# V0_1.net
KiCad netlist of a schematic drawn in EAGLE
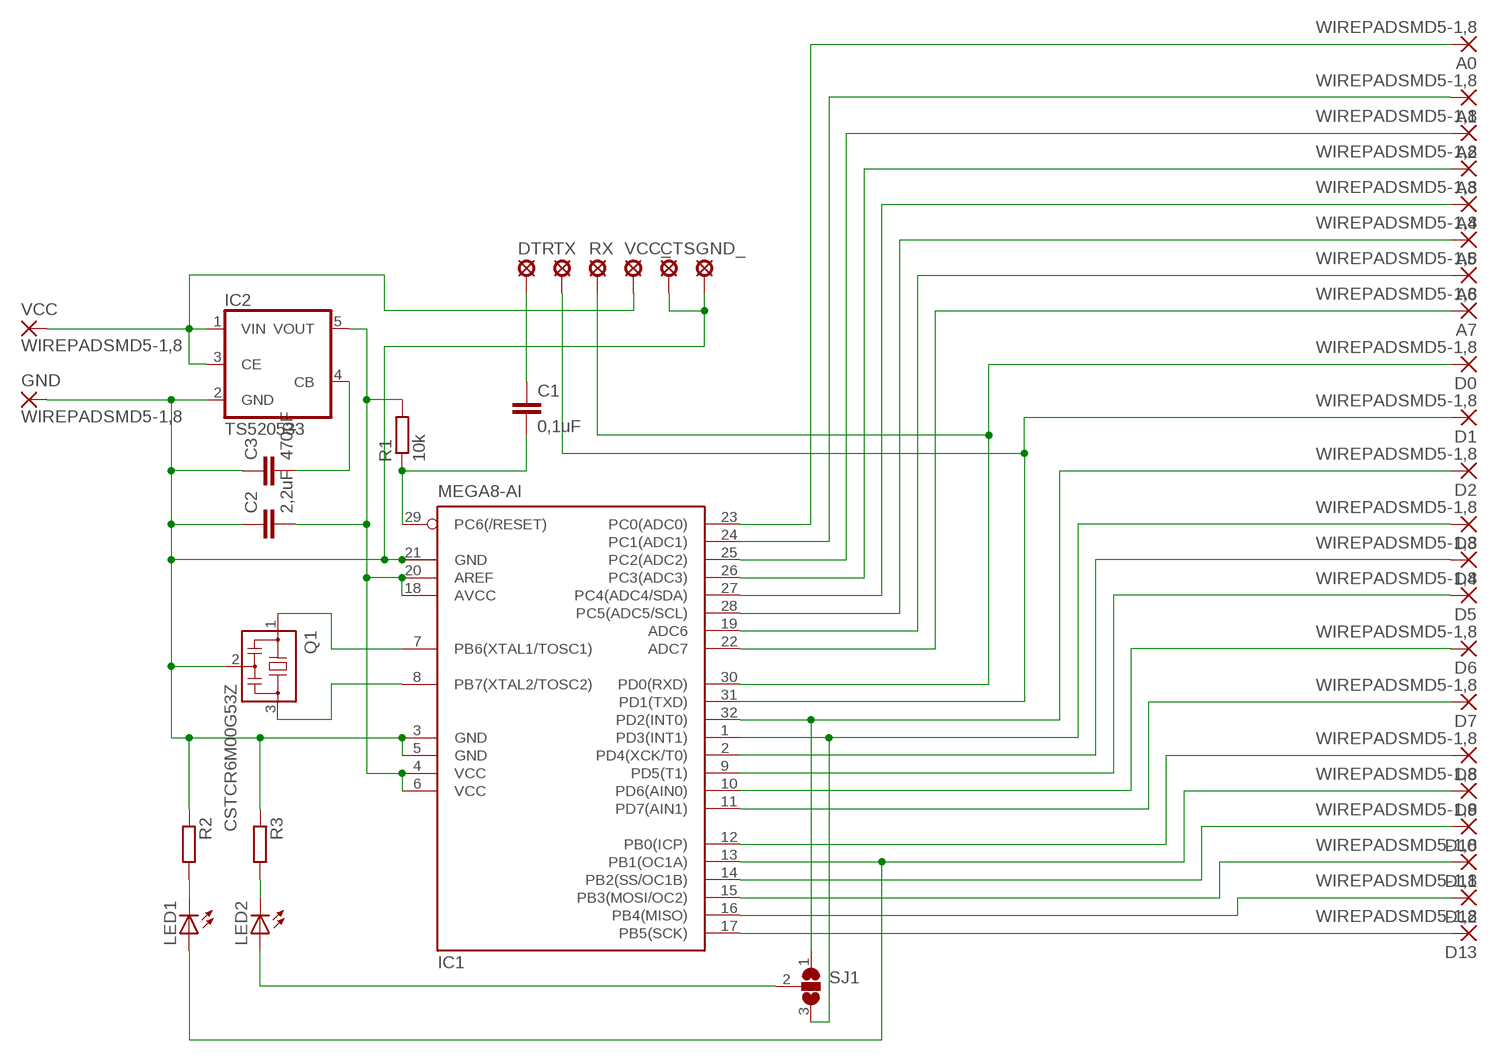
[diagram p0: schematic, sheet 1]

(export (version "E")
  (design (tool "Eeschema 10.0.6"))
  (components
    (comp (ref "A0")
      (value "WIREPADSMD5-1,8")
      (footprint "eagle-import:5-1,8")
      (libsource (lib "eagle-import") (part "WIREPADSMD5-1,8"))
    )
    (comp (ref "A1")
      (value "WIREPADSMD5-1,8")
      (footprint "eagle-import:5-1,8")
      (libsource (lib "eagle-import") (part "WIREPADSMD5-1,8"))
    )
    (comp (ref "A2")
      (value "WIREPADSMD5-1,8")
      (footprint "eagle-import:5-1,8")
      (libsource (lib "eagle-import") (part "WIREPADSMD5-1,8"))
    )
    (comp (ref "A3")
      (value "WIREPADSMD5-1,8")
      (footprint "eagle-import:5-1,8")
      (libsource (lib "eagle-import") (part "WIREPADSMD5-1,8"))
    )
    (comp (ref "A4")
      (value "WIREPADSMD5-1,8")
      (footprint "eagle-import:5-1,8")
      (libsource (lib "eagle-import") (part "WIREPADSMD5-1,8"))
    )
    (comp (ref "A5")
      (value "WIREPADSMD5-1,8")
      (footprint "eagle-import:5-1,8")
      (libsource (lib "eagle-import") (part "WIREPADSMD5-1,8"))
    )
    (comp (ref "A6")
      (value "WIREPADSMD5-1,8")
      (footprint "eagle-import:5-1,8")
      (libsource (lib "eagle-import") (part "WIREPADSMD5-1,8"))
    )
    (comp (ref "A7")
      (value "WIREPADSMD5-1,8")
      (footprint "eagle-import:5-1,8")
      (libsource (lib "eagle-import") (part "WIREPADSMD5-1,8"))
    )
    (comp (ref "C1")
      (value "0,1uF")
      (footprint "eagle-import:C0603")
      (libsource (lib "eagle-import") (part "C-EUC0603"))
    )
    (comp (ref "C2")
      (value "2,2uF")
      (footprint "eagle-import:C0603")
      (libsource (lib "eagle-import") (part "C-EUC0603"))
    )
    (comp (ref "C3")
      (value "470pF")
      (footprint "eagle-import:C0603")
      (libsource (lib "eagle-import") (part "C-EUC0603"))
    )
    (comp (ref "CTS")
      (value "LSP10")
      (footprint "eagle-import:LSP10")
      (libsource (lib "eagle-import") (part "LSP10"))
    )
    (comp (ref "D0")
      (value "WIREPADSMD5-1,8")
      (footprint "eagle-import:5-1,8")
      (libsource (lib "eagle-import") (part "WIREPADSMD5-1,8"))
    )
    (comp (ref "D1")
      (value "WIREPADSMD5-1,8")
      (footprint "eagle-import:5-1,8")
      (libsource (lib "eagle-import") (part "WIREPADSMD5-1,8"))
    )
    (comp (ref "D2")
      (value "WIREPADSMD5-1,8")
      (footprint "eagle-import:5-1,8")
      (libsource (lib "eagle-import") (part "WIREPADSMD5-1,8"))
    )
    (comp (ref "D3")
      (value "WIREPADSMD5-1,8")
      (footprint "eagle-import:5-1,8")
      (libsource (lib "eagle-import") (part "WIREPADSMD5-1,8"))
    )
    (comp (ref "D4")
      (value "WIREPADSMD5-1,8")
      (footprint "eagle-import:5-1,8")
      (libsource (lib "eagle-import") (part "WIREPADSMD5-1,8"))
    )
    (comp (ref "D5")
      (value "WIREPADSMD5-1,8")
      (footprint "eagle-import:5-1,8")
      (libsource (lib "eagle-import") (part "WIREPADSMD5-1,8"))
    )
    (comp (ref "D6")
      (value "WIREPADSMD5-1,8")
      (footprint "eagle-import:5-1,8")
      (libsource (lib "eagle-import") (part "WIREPADSMD5-1,8"))
    )
    (comp (ref "D7")
      (value "WIREPADSMD5-1,8")
      (footprint "eagle-import:5-1,8")
      (libsource (lib "eagle-import") (part "WIREPADSMD5-1,8"))
    )
    (comp (ref "D8")
      (value "WIREPADSMD5-1,8")
      (footprint "eagle-import:5-1,8")
      (libsource (lib "eagle-import") (part "WIREPADSMD5-1,8"))
    )
    (comp (ref "D9")
      (value "WIREPADSMD5-1,8")
      (footprint "eagle-import:5-1,8")
      (libsource (lib "eagle-import") (part "WIREPADSMD5-1,8"))
    )
    (comp (ref "D10")
      (value "WIREPADSMD5-1,8")
      (footprint "eagle-import:5-1,8")
      (libsource (lib "eagle-import") (part "WIREPADSMD5-1,8"))
    )
    (comp (ref "D11")
      (value "WIREPADSMD5-1,8")
      (footprint "eagle-import:5-1,8")
      (libsource (lib "eagle-import") (part "WIREPADSMD5-1,8"))
    )
    (comp (ref "D12")
      (value "WIREPADSMD5-1,8")
      (footprint "eagle-import:5-1,8")
      (libsource (lib "eagle-import") (part "WIREPADSMD5-1,8"))
    )
    (comp (ref "D13")
      (value "WIREPADSMD5-1,8")
      (footprint "eagle-import:5-1,8")
      (libsource (lib "eagle-import") (part "WIREPADSMD5-1,8"))
    )
    (comp (ref "DTR")
      (value "LSP10")
      (footprint "eagle-import:LSP10")
      (libsource (lib "eagle-import") (part "LSP10"))
    )
    (comp (ref "GND")
      (value "WIREPADSMD5-1,8")
      (footprint "eagle-import:5-1,8")
      (libsource (lib "eagle-import") (part "WIREPADSMD5-1,8"))
    )
    (comp (ref "GND_")
      (value "LSP10")
      (footprint "eagle-import:LSP10")
      (libsource (lib "eagle-import") (part "LSP10"))
    )
    (comp (ref "IC1")
      (value "MEGA8-AI")
      (footprint "eagle-import:TQFP32-08")
      (fields (field (name "MPN") "ATMEGA8-16AU") (field (name "MPN_1") "ATMEGA328P-16AU"))
      (libsource (lib "eagle-import") (part "MEGA8-AI"))
    )
    (comp (ref "IC2")
      (value "TS520533")
      (footprint "eagle-import:SOT25")
      (libsource (lib "eagle-import") (part "TS520533"))
    )
    (comp (ref "LED1")
      (value "LEDCHIP-LED0603")
      (footprint "eagle-import:CHIP-LED0603")
      (libsource (lib "eagle-import") (part "LEDCHIP-LED0603"))
    )
    (comp (ref "LED2")
      (value "LEDCHIP-LED0603")
      (footprint "eagle-import:CHIP-LED0603")
      (libsource (lib "eagle-import") (part "LEDCHIP-LED0603"))
    )
    (comp (ref "Q1")
      (value "CSTCR6M00G53Z")
      (footprint "eagle-import:CSTCR6M")
      (fields (field (name "MPN") "CSTCR6M00G53-R0"))
      (libsource (lib "eagle-import") (part "CSTCR6M00G53Z"))
    )
    (comp (ref "R1")
      (value "10k")
      (footprint "eagle-import:R0603")
      (libsource (lib "eagle-import") (part "R-EU_R0603"))
    )
    (comp (ref "R2")
      (value "R-EU_R0603")
      (footprint "eagle-import:R0603")
      (libsource (lib "eagle-import") (part "R-EU_R0603"))
    )
    (comp (ref "R3")
      (value "R-EU_R0603")
      (footprint "eagle-import:R0603")
      (libsource (lib "eagle-import") (part "R-EU_R0603"))
    )
    (comp (ref "RX")
      (value "LSP10")
      (footprint "eagle-import:LSP10")
      (libsource (lib "eagle-import") (part "LSP10"))
    )
    (comp (ref "SJ1")
      (value "SJ2W")
      (footprint "eagle-import:SJ_2")
      (libsource (lib "eagle-import") (part "SJ2W"))
    )
    (comp (ref "TX")
      (value "LSP10")
      (footprint "eagle-import:LSP10")
      (libsource (lib "eagle-import") (part "LSP10"))
    )
    (comp (ref "VCC")
      (value "WIREPADSMD5-1,8")
      (footprint "eagle-import:5-1,8")
      (libsource (lib "eagle-import") (part "WIREPADSMD5-1,8"))
    )
    (comp (ref "VCC_")
      (value "LSP10")
      (footprint "eagle-import:LSP10")
      (libsource (lib "eagle-import") (part "LSP10"))
    )
  )
  (nets
    (net (code "1") (name "Net-(A0-P)") (class "Default")
      (node (ref "A0") (pin "1") (pinfunction "P_1") (pintype "passive"))
      (node (ref "IC1") (pin "23") (pinfunction "PC0(ADC0)_23") (pintype "bidirectional"))
    )
    (net (code "2") (name "Net-(A1-P)") (class "Default")
      (node (ref "A1") (pin "1") (pinfunction "P_1") (pintype "passive"))
      (node (ref "IC1") (pin "24") (pinfunction "PC1(ADC1)_24") (pintype "bidirectional"))
    )
    (net (code "3") (name "Net-(A2-P)") (class "Default")
      (node (ref "A2") (pin "1") (pinfunction "P_1") (pintype "passive"))
      (node (ref "IC1") (pin "25") (pinfunction "PC2(ADC2)_25") (pintype "bidirectional"))
    )
    (net (code "4") (name "Net-(A3-P)") (class "Default")
      (node (ref "A3") (pin "1") (pinfunction "P_1") (pintype "passive"))
      (node (ref "IC1") (pin "26") (pinfunction "PC3(ADC3)_26") (pintype "bidirectional"))
    )
    (net (code "5") (name "Net-(A4-P)") (class "Default")
      (node (ref "A4") (pin "1") (pinfunction "P_1") (pintype "passive"))
      (node (ref "IC1") (pin "27") (pinfunction "PC4(ADC4/SDA)_27") (pintype "bidirectional"))
    )
    (net (code "6") (name "Net-(A5-P)") (class "Default")
      (node (ref "A5") (pin "1") (pinfunction "P_1") (pintype "passive"))
      (node (ref "IC1") (pin "28") (pinfunction "PC5(ADC5/SCL)_28") (pintype "bidirectional"))
    )
    (net (code "7") (name "Net-(A6-P)") (class "Default")
      (node (ref "A6") (pin "1") (pinfunction "P_1") (pintype "passive"))
      (node (ref "IC1") (pin "19") (pinfunction "ADC6_19") (pintype "bidirectional"))
    )
    (net (code "8") (name "Net-(A7-P)") (class "Default")
      (node (ref "A7") (pin "1") (pinfunction "P_1") (pintype "passive"))
      (node (ref "IC1") (pin "22") (pinfunction "ADC7_22") (pintype "bidirectional"))
    )
    (net (code "9") (name "Net-(C1-Pad1)") (class "Default")
      (node (ref "C1") (pin "1") (pinfunction "1_1") (pintype "passive"))
      (node (ref "DTR") (pin "MP") (pinfunction "MP_MP") (pintype "passive"))
    )
    (net (code "10") (name "Net-(D0-P)") (class "Default")
      (node (ref "D0") (pin "1") (pinfunction "P_1") (pintype "passive"))
      (node (ref "IC1") (pin "30") (pinfunction "PD0(RXD)_30") (pintype "bidirectional"))
      (node (ref "RX") (pin "MP") (pinfunction "MP_MP") (pintype "passive"))
    )
    (net (code "11") (name "Net-(D1-P)") (class "Default")
      (node (ref "D1") (pin "1") (pinfunction "P_1") (pintype "passive"))
      (node (ref "IC1") (pin "31") (pinfunction "PD1(TXD)_31") (pintype "bidirectional"))
      (node (ref "TX") (pin "MP") (pinfunction "MP_MP") (pintype "passive"))
    )
    (net (code "12") (name "Net-(D2-P)") (class "Default")
      (node (ref "D2") (pin "1") (pinfunction "P_1") (pintype "passive"))
      (node (ref "IC1") (pin "32") (pinfunction "PD2(INT0)_32") (pintype "bidirectional"))
      (node (ref "SJ1") (pin "1") (pinfunction "1_1") (pintype "passive"))
    )
    (net (code "13") (name "Net-(D3-P)") (class "Default")
      (node (ref "D3") (pin "1") (pinfunction "P_1") (pintype "passive"))
      (node (ref "IC1") (pin "1") (pinfunction "PD3(INT1)_1") (pintype "bidirectional"))
      (node (ref "SJ1") (pin "3") (pinfunction "3_3") (pintype "passive"))
    )
    (net (code "14") (name "Net-(D4-P)") (class "Default")
      (node (ref "D4") (pin "1") (pinfunction "P_1") (pintype "passive"))
      (node (ref "IC1") (pin "2") (pinfunction "PD4(XCK/T0)_2") (pintype "bidirectional"))
    )
    (net (code "15") (name "Net-(D5-P)") (class "Default")
      (node (ref "D5") (pin "1") (pinfunction "P_1") (pintype "passive"))
      (node (ref "IC1") (pin "9") (pinfunction "PD5(T1)_9") (pintype "bidirectional"))
    )
    (net (code "16") (name "Net-(D6-P)") (class "Default")
      (node (ref "D6") (pin "1") (pinfunction "P_1") (pintype "passive"))
      (node (ref "IC1") (pin "10") (pinfunction "PD6(AIN0)_10") (pintype "bidirectional"))
    )
    (net (code "17") (name "Net-(D7-P)") (class "Default")
      (node (ref "D7") (pin "1") (pinfunction "P_1") (pintype "passive"))
      (node (ref "IC1") (pin "11") (pinfunction "PD7(AIN1)_11") (pintype "bidirectional"))
    )
    (net (code "18") (name "Net-(D8-P)") (class "Default")
      (node (ref "D8") (pin "1") (pinfunction "P_1") (pintype "passive"))
      (node (ref "IC1") (pin "12") (pinfunction "PB0(ICP)_12") (pintype "bidirectional"))
    )
    (net (code "19") (name "Net-(D9-P)") (class "Default")
      (node (ref "D9") (pin "1") (pinfunction "P_1") (pintype "passive"))
      (node (ref "IC1") (pin "13") (pinfunction "PB1(OC1A)_13") (pintype "bidirectional"))
      (node (ref "LED1") (pin "A") (pinfunction "A_A") (pintype "passive"))
    )
    (net (code "20") (name "Net-(D10-P)") (class "Default")
      (node (ref "D10") (pin "1") (pinfunction "P_1") (pintype "passive"))
      (node (ref "IC1") (pin "14") (pinfunction "PB2(SS/OC1B)_14") (pintype "bidirectional"))
    )
    (net (code "21") (name "Net-(D11-P)") (class "Default")
      (node (ref "D11") (pin "1") (pinfunction "P_1") (pintype "passive"))
      (node (ref "IC1") (pin "15") (pinfunction "PB3(MOSI/OC2)_15") (pintype "bidirectional"))
    )
    (net (code "22") (name "Net-(D12-P)") (class "Default")
      (node (ref "D12") (pin "1") (pinfunction "P_1") (pintype "passive"))
      (node (ref "IC1") (pin "16") (pinfunction "PB4(MISO)_16") (pintype "bidirectional"))
    )
    (net (code "23") (name "Net-(D13-P)") (class "Default")
      (node (ref "D13") (pin "1") (pinfunction "P_1") (pintype "passive"))
      (node (ref "IC1") (pin "17") (pinfunction "PB5(SCK)_17") (pintype "bidirectional"))
    )
    (net (code "24") (name "Net-(GND-P)") (class "Default")
      (node (ref "C2") (pin "1") (pinfunction "1_1") (pintype "passive"))
      (node (ref "C3") (pin "1") (pinfunction "1_1") (pintype "passive"))
      (node (ref "CTS") (pin "MP") (pinfunction "MP_MP") (pintype "passive"))
      (node (ref "GND") (pin "1") (pinfunction "P_1") (pintype "passive"))
      (node (ref "GND_") (pin "MP") (pinfunction "MP_MP") (pintype "passive"))
      (node (ref "IC1") (pin "21") (pinfunction "GND_21") (pintype "power_in"))
      (node (ref "IC1") (pin "3") (pinfunction "GND_3") (pintype "power_in"))
      (node (ref "IC1") (pin "5") (pinfunction "GND_5") (pintype "power_in"))
      (node (ref "IC2") (pin "2") (pinfunction "GND_2") (pintype "passive"))
      (node (ref "Q1") (pin "2") (pinfunction "2_2") (pintype "passive"))
      (node (ref "R2") (pin "1") (pinfunction "1_1") (pintype "passive"))
      (node (ref "R3") (pin "1") (pinfunction "1_1") (pintype "passive"))
    )
    (net (code "25") (name "Net-(IC1-AREF)") (class "Default")
      (node (ref "C2") (pin "2") (pinfunction "2_2") (pintype "passive"))
      (node (ref "IC1") (pin "18") (pinfunction "AVCC_18") (pintype "power_in"))
      (node (ref "IC1") (pin "20") (pinfunction "AREF_20") (pintype "passive"))
      (node (ref "IC1") (pin "4") (pinfunction "VCC_4") (pintype "power_in"))
      (node (ref "IC1") (pin "6") (pinfunction "VCC_6") (pintype "power_in"))
      (node (ref "IC2") (pin "5") (pinfunction "VOUT_5") (pintype "passive"))
      (node (ref "R1") (pin "2") (pinfunction "2_2") (pintype "passive"))
    )
    (net (code "26") (name "Net-(IC1-PB6(XTAL1{slash}TOSC1))") (class "Default")
      (node (ref "IC1") (pin "7") (pinfunction "PB6(XTAL1/TOSC1)_7") (pintype "bidirectional"))
      (node (ref "Q1") (pin "1") (pinfunction "1_1") (pintype "passive"))
    )
    (net (code "27") (name "Net-(IC1-PB7(XTAL2{slash}TOSC2))") (class "Default")
      (node (ref "IC1") (pin "8") (pinfunction "PB7(XTAL2/TOSC2)_8") (pintype "bidirectional"))
      (node (ref "Q1") (pin "3") (pinfunction "3_3") (pintype "passive"))
    )
    (net (code "28") (name "Net-(IC1-PC6({slash}RESET))") (class "Default")
      (node (ref "C1") (pin "2") (pinfunction "2_2") (pintype "passive"))
      (node (ref "IC1") (pin "29") (pinfunction "PC6(/RESET)_29") (pintype "bidirectional"))
      (node (ref "R1") (pin "1") (pinfunction "1_1") (pintype "passive"))
    )
    (net (code "29") (name "Net-(IC2-CB)") (class "Default")
      (node (ref "C3") (pin "2") (pinfunction "2_2") (pintype "passive"))
      (node (ref "IC2") (pin "4") (pinfunction "CB_4") (pintype "input"))
    )
    (net (code "30") (name "Net-(IC2-CE)") (class "Default")
      (node (ref "IC2") (pin "1") (pinfunction "VIN_1") (pintype "input"))
      (node (ref "IC2") (pin "3") (pinfunction "CE_3") (pintype "input"))
      (node (ref "VCC") (pin "1") (pinfunction "P_1") (pintype "passive"))
      (node (ref "VCC_") (pin "MP") (pinfunction "MP_MP") (pintype "passive"))
    )
    (net (code "31") (name "Net-(LED1-PadC)") (class "Default")
      (node (ref "LED1") (pin "C") (pinfunction "C_C") (pintype "passive"))
      (node (ref "R2") (pin "2") (pinfunction "2_2") (pintype "passive"))
    )
    (net (code "32") (name "Net-(LED2-PadA)") (class "Default")
      (node (ref "LED2") (pin "A") (pinfunction "A_A") (pintype "passive"))
      (node (ref "SJ1") (pin "2") (pinfunction "2_2") (pintype "passive"))
    )
    (net (code "33") (name "Net-(LED2-PadC)") (class "Default")
      (node (ref "LED2") (pin "C") (pinfunction "C_C") (pintype "passive"))
      (node (ref "R3") (pin "2") (pinfunction "2_2") (pintype "passive"))
    )
  )
)
